# Buzzer.net
KiCad netlist of a schematic drawn in Altium Designer
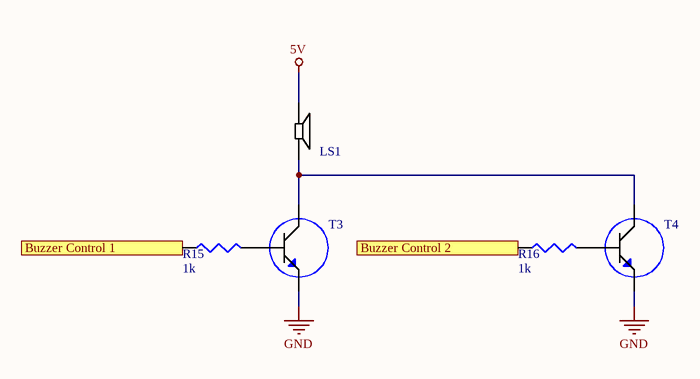
[diagram p0: Buzzer.SchDoc]

(export (version "E")
  (design (tool "Eeschema 10.0.6"))
  (components
    (comp (ref "LS1")
      (value "CT-1205C-SMT")
      (footprint "CUI_CT-1205C-SMT")
      (fields (field (name "MF") "CUI Inc.") (field (name "MP") "CT-1205C-SMT-TR"))
      (libsource (lib "AvionicsParts") (part "Buzzer"))
    )
    (comp (ref "R15")
      (value "1k")
      (description "Resistor")
      (fields (field (name "Comment") "Res3") (field (name "PUBLISHER") "Altium Limited"))
      (libsource (lib "Miscellaneous Devices") (part "Res3"))
    )
    (comp (ref "R16")
      (value "1k")
      (description "Resistor")
      (fields (field (name "Comment") "Res3") (field (name "PUBLISHER") "Altium Limited"))
      (libsource (lib "Miscellaneous Devices") (part "Res3"))
    )
    (comp (ref "T3")
      (value "MMBT2222ALT1")
      (footprint "BJT")
      (description "Trans NPN 40V 0.6A SOT23")
      (fields (field (name "MF") "ON Semiconductor"))
      (libsource (lib "AvionicsParts") (part "BJT NPN"))
    )
    (comp (ref "T4")
      (value "MMBT2222ALT1")
      (footprint "BJT")
      (description "Trans NPN 40V 0.6A SOT23")
      (fields (field (name "MF") "ON Semiconductor"))
      (libsource (lib "AvionicsParts") (part "BJT NPN"))
    )
  )
  (nets
    (net (code "1") (name "/Buzzer Control 1") (class "Default")
      (node (ref "R15") (pin "1") (pinfunction "1_1") (pintype "passive"))
    )
    (net (code "2") (name "/Buzzer Control 2") (class "Default")
      (node (ref "R16") (pin "1") (pinfunction "1_1") (pintype "passive"))
    )
    (net (code "3") (name "5V") (class "Default")
      (node (ref "LS1") (pin "2") (pinfunction "2_2") (pintype "passive"))
    )
    (net (code "4") (name "GND") (class "Default")
      (node (ref "T3") (pin "2") (pinfunction "E_2") (pintype "passive"))
      (node (ref "T4") (pin "2") (pinfunction "E_2") (pintype "passive"))
    )
    (net (code "5") (name "Net-(T3-B)") (class "Default")
      (node (ref "R15") (pin "2") (pinfunction "2_2") (pintype "passive"))
      (node (ref "T3") (pin "1") (pinfunction "B_1") (pintype "passive"))
    )
    (net (code "6") (name "Net-(T3-C)") (class "Default")
      (node (ref "LS1") (pin "1") (pinfunction "1_1") (pintype "passive"))
      (node (ref "T3") (pin "3") (pinfunction "C_3") (pintype "passive"))
      (node (ref "T4") (pin "3") (pinfunction "C_3") (pintype "passive"))
    )
    (net (code "7") (name "Net-(T4-B)") (class "Default")
      (node (ref "R16") (pin "2") (pinfunction "2_2") (pintype "passive"))
      (node (ref "T4") (pin "1") (pinfunction "B_1") (pintype "passive"))
    )
  )
)
